# Tespen.net
KiCad netlist of a schematic drawn in Altium Designer
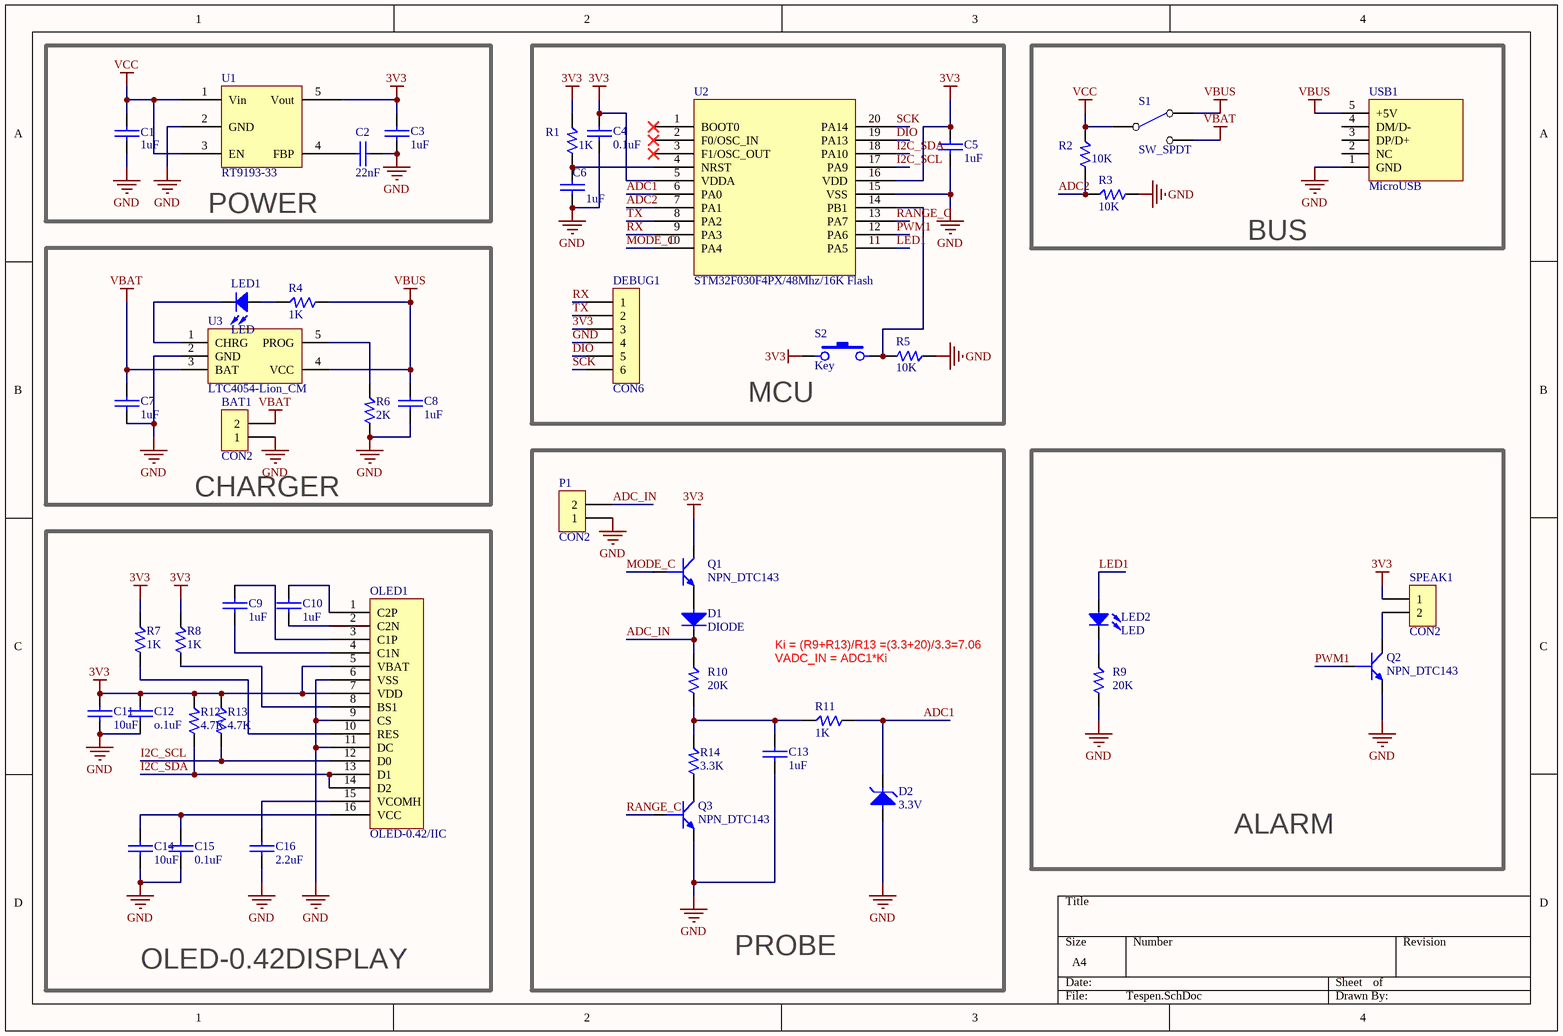
[diagram p0: Tespen.SchDoc]

(export (version "E")
  (design (tool "Eeschema 10.0.6"))
  (components
    (comp (ref "BAT1")
      (value "CON2")
      (footprint "SIP2")
      (description "Connector")
      (libsource (lib "DXP_LibraryCM") (part "CON2"))
    )
    (comp (ref "C1")
      (value "1uF")
      (footprint "0603C")
      (description "Capacitor")
      (libsource (lib "DXP_LibraryCM") (part "CAP"))
    )
    (comp (ref "C2")
      (value "22nF")
      (footprint "0603C")
      (description "Capacitor")
      (libsource (lib "DXP_LibraryCM") (part "CAP"))
    )
    (comp (ref "C3")
      (value "1uF")
      (footprint "0603C")
      (description "Capacitor")
      (libsource (lib "DXP_LibraryCM") (part "CAP"))
    )
    (comp (ref "C4")
      (value "0.1uF")
      (footprint "0603C")
      (description "Capacitor")
      (libsource (lib "DXP_LibraryCM") (part "CAP"))
    )
    (comp (ref "C5")
      (value "1uF")
      (footprint "0603C")
      (description "Capacitor")
      (libsource (lib "DXP_LibraryCM") (part "CAP"))
    )
    (comp (ref "C6")
      (value "1uF")
      (footprint "0603C")
      (description "Capacitor")
      (libsource (lib "DXP_LibraryCM") (part "CAP"))
    )
    (comp (ref "C7")
      (value "1uF")
      (footprint "0603C")
      (description "Capacitor")
      (libsource (lib "DXP_LibraryCM") (part "CAP"))
    )
    (comp (ref "C8")
      (value "1uF")
      (footprint "0603C")
      (description "Capacitor")
      (libsource (lib "DXP_LibraryCM") (part "CAP"))
    )
    (comp (ref "C9")
      (value "1uF")
      (footprint "0603C")
      (description "Capacitor")
      (libsource (lib "DXP_LibraryCM") (part "CAP"))
    )
    (comp (ref "C10")
      (value "1uF")
      (footprint "0603C")
      (description "Capacitor")
      (libsource (lib "DXP_LibraryCM") (part "CAP"))
    )
    (comp (ref "C11")
      (value "10uF")
      (footprint "0603C")
      (description "Capacitor")
      (libsource (lib "DXP_LibraryCM") (part "CAP"))
    )
    (comp (ref "C12")
      (value "o.1uF")
      (footprint "0603C")
      (description "Capacitor")
      (libsource (lib "DXP_LibraryCM") (part "CAP"))
    )
    (comp (ref "C13")
      (value "1uF")
      (footprint "0603C")
      (description "Capacitor")
      (libsource (lib "DXP_LibraryCM") (part "CAP"))
    )
    (comp (ref "C14")
      (value "10uF")
      (footprint "0603C")
      (description "Capacitor")
      (libsource (lib "DXP_LibraryCM") (part "CAP"))
    )
    (comp (ref "C15")
      (value "0.1uF")
      (footprint "0603C")
      (description "Capacitor")
      (libsource (lib "DXP_LibraryCM") (part "CAP"))
    )
    (comp (ref "C16")
      (value "2.2uF")
      (footprint "0603C")
      (description "Capacitor")
      (libsource (lib "DXP_LibraryCM") (part "CAP"))
    )
    (comp (ref "D1") (value "DIODE") (footprint "SOD-123") (libsource (lib "DXP_LibraryCM") (part "DIODE")))
    (comp (ref "D2")
      (value "3.3V")
      (footprint "SOD-123")
      (description "TVS")
      (libsource (lib "DXP_LibraryCM") (part "DIODE_ZENER"))
    )
    (comp (ref "DEBUG1")
      (value "CON6")
      (footprint "SIP6")
      (description "Connector")
      (libsource (lib "DXP_LibraryCM") (part "CON6"))
    )
    (comp (ref "LED1") (value "LED") (footprint "1206D") (libsource (lib "DXP_LibraryCM") (part "LED")))
    (comp (ref "LED2") (value "LED") (footprint "1206D") (libsource (lib "DXP_LibraryCM") (part "LED")))
    (comp (ref "OLED1") (value "OLED-0.42/IIC") (libsource (lib "模块") (part "OLED-0.42-IIC")))
    (comp (ref "P1")
      (value "CON2")
      (footprint "KF508V-2")
      (description "Connector")
      (libsource (lib "DXP_LibraryCM") (part "CON2"))
    )
    (comp (ref "Q1")
      (value "NPN_DTC143")
      (footprint "SOT-523")
      (libsource (lib "DXP_LibraryCM") (part "NPN_DTC143"))
    )
    (comp (ref "Q2")
      (value "NPN_DTC143")
      (footprint "SOT-523")
      (libsource (lib "DXP_LibraryCM") (part "NPN_DTC143"))
    )
    (comp (ref "Q3")
      (value "NPN_DTC143")
      (footprint "SOT-523")
      (libsource (lib "DXP_LibraryCM") (part "NPN_DTC143"))
    )
    (comp (ref "R1")
      (value "1K")
      (footprint "0603")
      (description "Potentiometer")
      (libsource (lib "DXP_LibraryCM") (part "RES"))
    )
    (comp (ref "R2")
      (value "10K")
      (footprint "0603")
      (description "Potentiometer")
      (libsource (lib "DXP_LibraryCM") (part "RES"))
    )
    (comp (ref "R3")
      (value "10K")
      (footprint "0603")
      (description "Potentiometer")
      (libsource (lib "DXP_LibraryCM") (part "RES"))
    )
    (comp (ref "R4")
      (value "1K")
      (footprint "0603")
      (description "Potentiometer")
      (libsource (lib "DXP_LibraryCM") (part "RES"))
    )
    (comp (ref "R5")
      (value "10K")
      (footprint "0603")
      (description "Potentiometer")
      (libsource (lib "DXP_LibraryCM") (part "RES"))
    )
    (comp (ref "R6")
      (value "2K")
      (footprint "0603")
      (description "Potentiometer")
      (libsource (lib "DXP_LibraryCM") (part "RES"))
    )
    (comp (ref "R7")
      (value "1K")
      (footprint "0603")
      (description "Potentiometer")
      (libsource (lib "DXP_LibraryCM") (part "RES"))
    )
    (comp (ref "R8")
      (value "1K")
      (footprint "0603")
      (description "Potentiometer")
      (libsource (lib "DXP_LibraryCM") (part "RES"))
    )
    (comp (ref "R9")
      (value "20K")
      (footprint "0603")
      (description "Potentiometer")
      (libsource (lib "DXP_LibraryCM") (part "RES"))
    )
    (comp (ref "R10")
      (value "20K")
      (footprint "0603")
      (description "Potentiometer")
      (libsource (lib "DXP_LibraryCM") (part "RES"))
    )
    (comp (ref "R11")
      (value "1K")
      (footprint "0603")
      (description "Potentiometer")
      (libsource (lib "DXP_LibraryCM") (part "RES"))
    )
    (comp (ref "R12")
      (value "4.7K")
      (footprint "0603")
      (description "Potentiometer")
      (libsource (lib "DXP_LibraryCM") (part "RES"))
    )
    (comp (ref "R13")
      (value "4.7K")
      (footprint "0603")
      (description "Potentiometer")
      (libsource (lib "DXP_LibraryCM") (part "RES"))
    )
    (comp (ref "R14")
      (value "3.3K")
      (footprint "0603")
      (description "Potentiometer")
      (libsource (lib "DXP_LibraryCM") (part "RES"))
    )
    (comp (ref "S1") (value "SW_SPDT") (libsource (lib "DXP_LibraryCM") (part "SW_SPDT")))
    (comp (ref "S2") (value "Key") (footprint "KEY_DIP") (libsource (lib "DXP_LibraryCM") (part "Key")))
    (comp (ref "SPEAK1")
      (value "CON2")
      (footprint "KF508V-2")
      (description "Connector")
      (libsource (lib "") (part "CON2_1"))
    )
    (comp (ref "U1")
      (value "RT9193-33")
      (footprint "SOT-23-5")
      (libsource (lib "DXP_LibraryCM") (part "RT9193-xx"))
    )
    (comp (ref "U2")
      (value "STM32F030F4PX/48Mhz/16K Flash")
      (footprint "TSSOP20-44")
      (libsource (lib "微处理器") (part "STM32F030F4PX"))
    )
    (comp (ref "U3") (value "LTC4054-Lion_CM") (libsource (lib "集成元器件") (part "LTC4054")))
    (comp (ref "USB1")
      (value "MicroUSB")
      (footprint "USB/Mic-5SB")
      (libsource (lib "DXP_LibraryCM") (part "USBmini"))
    )
  )
  (nets
    (net (code "1") (name "/ADC1") (class "Default")
      (node (ref "D2") (pin "2") (pinfunction "2_2") (pintype "passive"))
      (node (ref "R11") (pin "1") (pinfunction "1_1") (pintype "passive"))
      (node (ref "U2") (pin "6") (pinfunction "PA0_6") (pintype "passive"))
    )
    (net (code "2") (name "/ADC2") (class "Default")
      (node (ref "R2") (pin "1") (pinfunction "1_1") (pintype "passive"))
      (node (ref "R3") (pin "2") (pinfunction "2_2") (pintype "passive"))
      (node (ref "U2") (pin "7") (pinfunction "PA1_7") (pintype "passive"))
    )
    (net (code "3") (name "/ADC_IN") (class "Default")
      (node (ref "D1") (pin "2") (pinfunction "2_2") (pintype "passive"))
      (node (ref "P1") (pin "2") (pinfunction "2_2") (pintype "passive"))
      (node (ref "R10") (pin "2") (pinfunction "2_2") (pintype "passive"))
    )
    (net (code "4") (name "/DIO") (class "Default")
      (node (ref "DEBUG1") (pin "5") (pinfunction "5_5") (pintype "passive"))
      (node (ref "U2") (pin "19") (pinfunction "PA13_19") (pintype "passive"))
    )
    (net (code "5") (name "/I2C_SCL") (class "Default")
      (node (ref "OLED1") (pin "12") (pinfunction "D0_12") (pintype "passive"))
      (node (ref "R13") (pin "1") (pinfunction "1_1") (pintype "passive"))
      (node (ref "U2") (pin "17") (pinfunction "PA9_17") (pintype "passive"))
    )
    (net (code "6") (name "/I2C_SDA") (class "Default")
      (node (ref "OLED1") (pin "13") (pinfunction "D1_13") (pintype "passive"))
      (node (ref "OLED1") (pin "14") (pinfunction "D2_14") (pintype "passive"))
      (node (ref "R12") (pin "1") (pinfunction "1_1") (pintype "passive"))
      (node (ref "U2") (pin "18") (pinfunction "PA10_18") (pintype "passive"))
    )
    (net (code "7") (name "/LED1") (class "Default")
      (node (ref "LED2") (pin "1") (pinfunction "1_1") (pintype "passive"))
      (node (ref "U2") (pin "11") (pinfunction "PA5_11") (pintype "passive"))
    )
    (net (code "8") (name "/MODE_C") (class "Default")
      (node (ref "Q1") (pin "1") (pinfunction "1_1") (pintype "passive"))
      (node (ref "U2") (pin "10") (pinfunction "PA4_10") (pintype "passive"))
    )
    (net (code "9") (name "/PWM1") (class "Default")
      (node (ref "Q2") (pin "1") (pinfunction "1_1") (pintype "passive"))
      (node (ref "U2") (pin "12") (pinfunction "PA6_12") (pintype "passive"))
    )
    (net (code "10") (name "/RANGE_C") (class "Default")
      (node (ref "Q3") (pin "1") (pinfunction "1_1") (pintype "passive"))
      (node (ref "U2") (pin "13") (pinfunction "PA7_13") (pintype "passive"))
    )
    (net (code "11") (name "/RX") (class "Default")
      (node (ref "DEBUG1") (pin "1") (pinfunction "1_1") (pintype "passive"))
      (node (ref "U2") (pin "9") (pinfunction "PA3_9") (pintype "passive"))
    )
    (net (code "12") (name "/SCK") (class "Default")
      (node (ref "DEBUG1") (pin "6") (pinfunction "6_6") (pintype "passive"))
      (node (ref "U2") (pin "20") (pinfunction "PA14_20") (pintype "passive"))
    )
    (net (code "13") (name "/TX") (class "Default")
      (node (ref "DEBUG1") (pin "2") (pinfunction "2_2") (pintype "passive"))
      (node (ref "U2") (pin "8") (pinfunction "PA2_8") (pintype "passive"))
    )
    (net (code "14") (name "3V3") (class "Default")
      (node (ref "C11") (pin "1") (pinfunction "1_1") (pintype "passive"))
      (node (ref "C12") (pin "1") (pinfunction "1_1") (pintype "passive"))
      (node (ref "C3") (pin "1") (pinfunction "1_1") (pintype "passive"))
      (node (ref "C4") (pin "1") (pinfunction "1_1") (pintype "passive"))
      (node (ref "C5") (pin "1") (pinfunction "1_1") (pintype "passive"))
      (node (ref "DEBUG1") (pin "3") (pinfunction "3_3") (pintype "passive"))
      (node (ref "OLED1") (pin "5") (pinfunction "VBAT_5") (pintype "passive"))
      (node (ref "OLED1") (pin "7") (pinfunction "VDD_7") (pintype "passive"))
      (node (ref "Q1") (pin "3") (pinfunction "3_3") (pintype "passive"))
      (node (ref "R1") (pin "2") (pinfunction "2_2") (pintype "passive"))
      (node (ref "R12") (pin "2") (pinfunction "2_2") (pintype "passive"))
      (node (ref "R13") (pin "2") (pinfunction "2_2") (pintype "passive"))
      (node (ref "R7") (pin "2") (pinfunction "2_2") (pintype "passive"))
      (node (ref "R8") (pin "2") (pinfunction "2_2") (pintype "passive"))
      (node (ref "S2") (pin "1") (pinfunction "1_1") (pintype "passive"))
      (node (ref "SPEAK1") (pin "1") (pinfunction "1_1") (pintype "passive"))
      (node (ref "U1") (pin "5") (pinfunction "Vout_5") (pintype "passive"))
      (node (ref "U2") (pin "16") (pinfunction "VDD_16") (pintype "passive"))
      (node (ref "U2") (pin "5") (pinfunction "VDDA_5") (pintype "passive"))
    )
    (net (code "15") (name "GND") (class "Default")
      (node (ref "BAT1") (pin "1") (pinfunction "1_1") (pintype "passive"))
      (node (ref "C1") (pin "2") (pinfunction "2_2") (pintype "passive"))
      (node (ref "C11") (pin "2") (pinfunction "2_2") (pintype "passive"))
      (node (ref "C12") (pin "2") (pinfunction "2_2") (pintype "passive"))
      (node (ref "C13") (pin "2") (pinfunction "2_2") (pintype "passive"))
      (node (ref "C14") (pin "2") (pinfunction "2_2") (pintype "passive"))
      (node (ref "C15") (pin "2") (pinfunction "2_2") (pintype "passive"))
      (node (ref "C16") (pin "2") (pinfunction "2_2") (pintype "passive"))
      (node (ref "C2") (pin "2") (pinfunction "2_2") (pintype "passive"))
      (node (ref "C3") (pin "2") (pinfunction "2_2") (pintype "passive"))
      (node (ref "C4") (pin "2") (pinfunction "2_2") (pintype "passive"))
      (node (ref "C5") (pin "2") (pinfunction "2_2") (pintype "passive"))
      (node (ref "C6") (pin "2") (pinfunction "2_2") (pintype "passive"))
      (node (ref "C7") (pin "2") (pinfunction "2_2") (pintype "passive"))
      (node (ref "C8") (pin "2") (pinfunction "2_2") (pintype "passive"))
      (node (ref "D2") (pin "1") (pinfunction "1_1") (pintype "passive"))
      (node (ref "DEBUG1") (pin "4") (pinfunction "4_4") (pintype "passive"))
      (node (ref "OLED1") (pin "11") (pinfunction "DC_11") (pintype "passive"))
      (node (ref "OLED1") (pin "6") (pinfunction "VSS_6") (pintype "passive"))
      (node (ref "OLED1") (pin "9") (pinfunction "CS_9") (pintype "passive"))
      (node (ref "P1") (pin "1") (pinfunction "1_1") (pintype "passive"))
      (node (ref "Q2") (pin "2") (pinfunction "2_2") (pintype "passive"))
      (node (ref "Q3") (pin "2") (pinfunction "2_2") (pintype "passive"))
      (node (ref "R3") (pin "1") (pinfunction "1_1") (pintype "passive"))
      (node (ref "R5") (pin "2") (pinfunction "2_2") (pintype "passive"))
      (node (ref "R6") (pin "1") (pinfunction "1_1") (pintype "passive"))
      (node (ref "R9") (pin "1") (pinfunction "1_1") (pintype "passive"))
      (node (ref "U1") (pin "2") (pinfunction "GND_2") (pintype "passive"))
      (node (ref "U2") (pin "15") (pinfunction "VSS_15") (pintype "passive"))
      (node (ref "U3") (pin "2") (pinfunction "GND_2") (pintype "passive"))
      (node (ref "USB1") (pin "1") (pinfunction "GND_1") (pintype "passive"))
    )
    (net (code "16") (name "Net-(C13-Pad1)") (class "Default")
      (node (ref "C13") (pin "1") (pinfunction "1_1") (pintype "passive"))
      (node (ref "R10") (pin "1") (pinfunction "1_1") (pintype "passive"))
      (node (ref "R11") (pin "2") (pinfunction "2_2") (pintype "passive"))
      (node (ref "R14") (pin "2") (pinfunction "2_2") (pintype "passive"))
    )
    (net (code "17") (name "Net-(D1-Pad1)") (class "Default")
      (node (ref "D1") (pin "1") (pinfunction "1_1") (pintype "passive"))
      (node (ref "Q1") (pin "2") (pinfunction "2_2") (pintype "passive"))
    )
    (net (code "18") (name "Net-(LED1-Pad1)") (class "Default")
      (node (ref "LED1") (pin "1") (pinfunction "1_1") (pintype "passive"))
      (node (ref "R4") (pin "2") (pinfunction "2_2") (pintype "passive"))
    )
    (net (code "19") (name "Net-(LED2-Pad2)") (class "Default")
      (node (ref "LED2") (pin "2") (pinfunction "2_2") (pintype "passive"))
      (node (ref "R9") (pin "2") (pinfunction "2_2") (pintype "passive"))
    )
    (net (code "20") (name "Net-(OLED1-BS1)") (class "Default")
      (node (ref "OLED1") (pin "8") (pinfunction "BS1_8") (pintype "passive"))
      (node (ref "R8") (pin "1") (pinfunction "1_1") (pintype "passive"))
    )
    (net (code "21") (name "Net-(OLED1-C1N)") (class "Default")
      (node (ref "C9") (pin "2") (pinfunction "2_2") (pintype "passive"))
      (node (ref "OLED1") (pin "4") (pinfunction "C1N_4") (pintype "passive"))
    )
    (net (code "22") (name "Net-(OLED1-C1P)") (class "Default")
      (node (ref "C9") (pin "1") (pinfunction "1_1") (pintype "passive"))
      (node (ref "OLED1") (pin "3") (pinfunction "C1P_3") (pintype "passive"))
    )
    (net (code "23") (name "Net-(OLED1-C2N)") (class "Default")
      (node (ref "C10") (pin "2") (pinfunction "2_2") (pintype "passive"))
      (node (ref "OLED1") (pin "2") (pinfunction "C2N_2") (pintype "passive"))
    )
    (net (code "24") (name "Net-(OLED1-C2P)") (class "Default")
      (node (ref "C10") (pin "1") (pinfunction "1_1") (pintype "passive"))
      (node (ref "OLED1") (pin "1") (pinfunction "C2P_1") (pintype "passive"))
    )
    (net (code "25") (name "Net-(OLED1-RES)") (class "Default")
      (node (ref "OLED1") (pin "10") (pinfunction "RES_10") (pintype "passive"))
      (node (ref "R7") (pin "1") (pinfunction "1_1") (pintype "passive"))
    )
    (net (code "26") (name "Net-(OLED1-VCC)") (class "Default")
      (node (ref "C14") (pin "1") (pinfunction "1_1") (pintype "passive"))
      (node (ref "C15") (pin "1") (pinfunction "1_1") (pintype "passive"))
      (node (ref "OLED1") (pin "16") (pinfunction "VCC_16") (pintype "passive"))
    )
    (net (code "27") (name "Net-(OLED1-VCOMH)") (class "Default")
      (node (ref "C16") (pin "1") (pinfunction "1_1") (pintype "passive"))
      (node (ref "OLED1") (pin "15") (pinfunction "VCOMH_15") (pintype "passive"))
    )
    (net (code "28") (name "Net-(Q2-Pad3)") (class "Default")
      (node (ref "Q2") (pin "3") (pinfunction "3_3") (pintype "passive"))
      (node (ref "SPEAK1") (pin "2") (pinfunction "2_2") (pintype "passive"))
    )
    (net (code "29") (name "Net-(Q3-Pad3)") (class "Default")
      (node (ref "Q3") (pin "3") (pinfunction "3_3") (pintype "passive"))
      (node (ref "R14") (pin "1") (pinfunction "1_1") (pintype "passive"))
    )
    (net (code "30") (name "Net-(U1-FBP)") (class "Default")
      (node (ref "C2") (pin "1") (pinfunction "1_1") (pintype "passive"))
      (node (ref "U1") (pin "4") (pinfunction "FBP_4") (pintype "passive"))
    )
    (net (code "31") (name "Net-(U2-NRST)") (class "Default")
      (node (ref "C6") (pin "1") (pinfunction "1_1") (pintype "passive"))
      (node (ref "R1") (pin "1") (pinfunction "1_1") (pintype "passive"))
      (node (ref "U2") (pin "4") (pinfunction "NRST_4") (pintype "passive"))
    )
    (net (code "32") (name "Net-(U2-PB1)") (class "Default")
      (node (ref "R5") (pin "1") (pinfunction "1_1") (pintype "passive"))
      (node (ref "S2") (pin "2") (pinfunction "2_2") (pintype "passive"))
      (node (ref "U2") (pin "14") (pinfunction "PB1_14") (pintype "passive"))
    )
    (net (code "33") (name "Net-(U3-CHRG)") (class "Default")
      (node (ref "LED1") (pin "2") (pinfunction "2_2") (pintype "passive"))
      (node (ref "U3") (pin "1") (pinfunction "CHRG_1") (pintype "passive"))
    )
    (net (code "34") (name "Net-(U3-PROG)") (class "Default")
      (node (ref "R6") (pin "2") (pinfunction "2_2") (pintype "passive"))
      (node (ref "U3") (pin "5") (pinfunction "PROG_5") (pintype "passive"))
    )
    (net (code "35") (name "VBAT") (class "Default")
      (node (ref "BAT1") (pin "2") (pinfunction "2_2") (pintype "passive"))
      (node (ref "C7") (pin "1") (pinfunction "1_1") (pintype "passive"))
      (node (ref "S1") (pin "3") (pinfunction "NO_3") (pintype "passive"))
      (node (ref "U3") (pin "3") (pinfunction "BAT_3") (pintype "passive"))
    )
    (net (code "36") (name "VBUS") (class "Default")
      (node (ref "C8") (pin "1") (pinfunction "1_1") (pintype "passive"))
      (node (ref "R4") (pin "1") (pinfunction "1_1") (pintype "passive"))
      (node (ref "S1") (pin "2") (pinfunction "NC_2") (pintype "passive"))
      (node (ref "U3") (pin "4") (pinfunction "VCC_4") (pintype "passive"))
      (node (ref "USB1") (pin "5") (pinfunction "+5V_5") (pintype "passive"))
    )
    (net (code "37") (name "VCC") (class "Default")
      (node (ref "C1") (pin "1") (pinfunction "1_1") (pintype "passive"))
      (node (ref "R2") (pin "2") (pinfunction "2_2") (pintype "passive"))
      (node (ref "S1") (pin "1") (pinfunction "COMMON_1") (pintype "passive"))
      (node (ref "U1") (pin "1") (pinfunction "Vin_1") (pintype "passive"))
      (node (ref "U1") (pin "3") (pinfunction "EN_3") (pintype "passive"))
    )
    (net (code "38") (name "unconnected-(U2-BOOT0-Pad1)") (class "Default")
      (node (ref "U2") (pin "1") (pinfunction "BOOT0_1") (pintype "passive+no_connect"))
    )
    (net (code "39") (name "unconnected-(U2-F0{slash}OSC_IN-Pad2)") (class "Default")
      (node (ref "U2") (pin "2") (pinfunction "F0/OSC_IN_2") (pintype "passive+no_connect"))
    )
    (net (code "40") (name "unconnected-(U2-F1{slash}OSC_OUT-Pad3)") (class "Default")
      (node (ref "U2") (pin "3") (pinfunction "F1/OSC_OUT_3") (pintype "passive+no_connect"))
    )
    (net (code "41") (name "unconnected-(USB1-DM{slash}D--Pad4)") (class "Default")
      (node (ref "USB1") (pin "4") (pinfunction "DM/D-_4") (pintype "passive"))
    )
    (net (code "42") (name "unconnected-(USB1-DP{slash}D+-Pad3)") (class "Default")
      (node (ref "USB1") (pin "3") (pinfunction "DP/D+_3") (pintype "passive"))
    )
    (net (code "43") (name "unconnected-(USB1-NC-Pad2)") (class "Default")
      (node (ref "USB1") (pin "2") (pinfunction "NC_2") (pintype "passive"))
    )
  )
)
